# board-ext.net
KiCad netlist of a schematic drawn in EAGLE
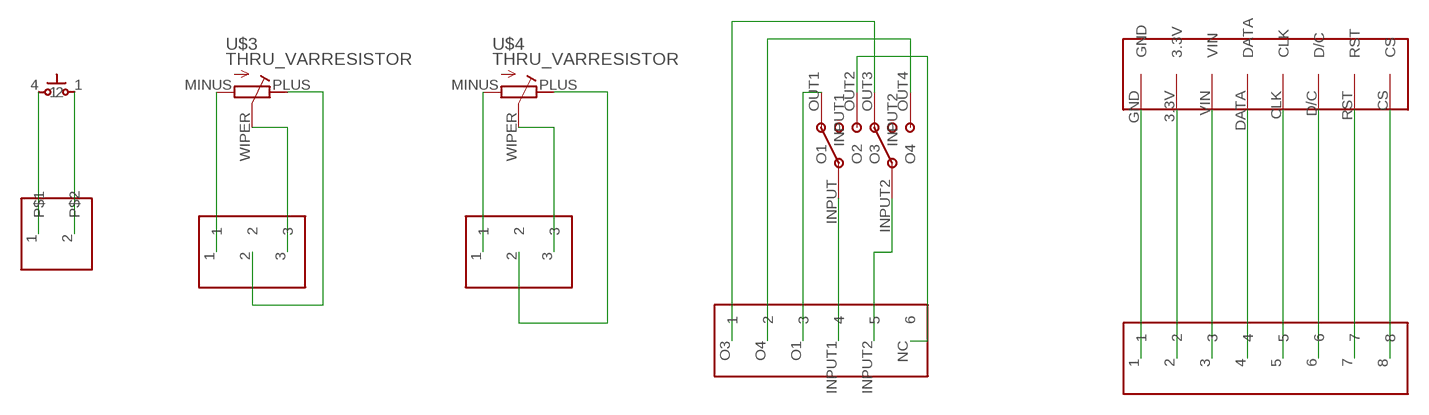
[diagram p0: schematic, sheet 1]

(export (version "E")
  (design (tool "Eeschema 10.0.6"))
  (components
    (comp (ref "U$1")
      (value "1X02")
      (footprint "eagle-import:1X02")
      (libsource (lib "eagle-import") (part "1X02"))
    )
    (comp (ref "U$2")
      (value "BUTTON_THRU")
      (footprint "eagle-import:PUSHBTN")
      (libsource (lib "eagle-import") (part "BUTTON_THRU"))
    )
    (comp (ref "U$3")
      (value "THRU_VARRESISTOR")
      (footprint "eagle-import:POT")
      (libsource (lib "eagle-import") (part "THRU_VARRESISTOR"))
    )
    (comp (ref "U$4")
      (value "THRU_VARRESISTOR")
      (footprint "eagle-import:POT")
      (libsource (lib "eagle-import") (part "THRU_VARRESISTOR"))
    )
    (comp (ref "U$5")
      (value "1X03")
      (footprint "eagle-import:1X03")
      (libsource (lib "eagle-import") (part "1X03"))
    )
    (comp (ref "U$6")
      (value "1X03")
      (footprint "eagle-import:1X03")
      (libsource (lib "eagle-import") (part "1X03"))
    )
    (comp (ref "U$7")
      (value "SWITCH_THRU")
      (footprint "eagle-import:DPDT")
      (libsource (lib "eagle-import") (part "SWITCH_THRU"))
    )
    (comp (ref "U$8")
      (value "1X06")
      (footprint "eagle-import:SWITCHHEAD")
      (libsource (lib "eagle-import") (part "1X06"))
    )
    (comp (ref "U$9")
      (value "OLED_THRU")
      (footprint "eagle-import:OLED_THRU")
      (libsource (lib "eagle-import") (part "OLED_THRU"))
    )
    (comp (ref "U$10")
      (value "1X08")
      (footprint "eagle-import:1X08")
      (libsource (lib "eagle-import") (part "1X08"))
    )
  )
  (nets
    (net (code "1") (name "Net-(U$1-P$1)") (class "Default")
      (node (ref "U$1") (pin "1") (pinfunction "P$1_1") (pintype "bidirectional"))
      (node (ref "U$2") (pin "4") (pinfunction "2_4") (pintype "bidirectional"))
    )
    (net (code "2") (name "Net-(U$1-P$2)") (class "Default")
      (node (ref "U$1") (pin "2") (pinfunction "P$2_2") (pintype "bidirectional"))
      (node (ref "U$2") (pin "1") (pinfunction "1_1") (pintype "bidirectional"))
    )
    (net (code "3") (name "Net-(U$3-PadMINUS)") (class "Default")
      (node (ref "U$3") (pin "MINUS") (pinfunction "MINUS_MINUS") (pintype "bidirectional"))
      (node (ref "U$5") (pin "1") (pinfunction "1_1") (pintype "bidirectional"))
    )
    (net (code "4") (name "Net-(U$3-PadPLUS)") (class "Default")
      (node (ref "U$3") (pin "PLUS") (pinfunction "PLUS_PLUS") (pintype "bidirectional"))
      (node (ref "U$5") (pin "2") (pinfunction "2_2") (pintype "bidirectional"))
    )
    (net (code "5") (name "Net-(U$3-PadWIPER)") (class "Default")
      (node (ref "U$3") (pin "WIPER") (pinfunction "WIPER_WIPER") (pintype "bidirectional"))
      (node (ref "U$5") (pin "3") (pinfunction "3_3") (pintype "bidirectional"))
    )
    (net (code "6") (name "Net-(U$4-PadMINUS)") (class "Default")
      (node (ref "U$4") (pin "MINUS") (pinfunction "MINUS_MINUS") (pintype "bidirectional"))
      (node (ref "U$6") (pin "1") (pinfunction "1_1") (pintype "bidirectional"))
    )
    (net (code "7") (name "Net-(U$4-PadPLUS)") (class "Default")
      (node (ref "U$4") (pin "PLUS") (pinfunction "PLUS_PLUS") (pintype "bidirectional"))
      (node (ref "U$6") (pin "2") (pinfunction "2_2") (pintype "bidirectional"))
    )
    (net (code "8") (name "Net-(U$4-PadWIPER)") (class "Default")
      (node (ref "U$4") (pin "WIPER") (pinfunction "WIPER_WIPER") (pintype "bidirectional"))
      (node (ref "U$6") (pin "3") (pinfunction "3_3") (pintype "bidirectional"))
    )
    (net (code "9") (name "Net-(U$7-INPUT1)") (class "Default")
      (node (ref "U$7") (pin "INPUT") (pinfunction "INPUT1_INPUT") (pintype "bidirectional"))
      (node (ref "U$8") (pin "INPUT1") (pinfunction "4_INPUT1") (pintype "bidirectional"))
    )
    (net (code "10") (name "Net-(U$7-O1)") (class "Default")
      (node (ref "U$7") (pin "OUT1") (pinfunction "O1_OUT1") (pintype "bidirectional"))
      (node (ref "U$8") (pin "O1") (pinfunction "3_O1") (pintype "bidirectional"))
    )
    (net (code "11") (name "Net-(U$7-O2)") (class "Default")
      (node (ref "U$7") (pin "OUT2") (pinfunction "O2_OUT2") (pintype "bidirectional"))
      (node (ref "U$8") (pin "NC") (pinfunction "6_NC") (pintype "bidirectional"))
    )
    (net (code "12") (name "Net-(U$7-O3)") (class "Default")
      (node (ref "U$7") (pin "OUT3") (pinfunction "O3_OUT3") (pintype "bidirectional"))
      (node (ref "U$8") (pin "O3") (pinfunction "1_O3") (pintype "bidirectional"))
    )
    (net (code "13") (name "Net-(U$7-O4)") (class "Default")
      (node (ref "U$7") (pin "OUT4") (pinfunction "O4_OUT4") (pintype "bidirectional"))
      (node (ref "U$8") (pin "O4") (pinfunction "2_O4") (pintype "bidirectional"))
    )
    (net (code "14") (name "Net-(U$8-5)") (class "Default")
      (node (ref "U$7") (pin "INPUT2") (pinfunction "INPUT2_INPUT2") (pintype "bidirectional"))
      (node (ref "U$8") (pin "INPUT2") (pinfunction "5_INPUT2") (pintype "bidirectional"))
    )
    (net (code "15") (name "Net-(U$10-Pad1)") (class "Default")
      (node (ref "U$10") (pin "1") (pinfunction "1_1") (pintype "bidirectional"))
      (node (ref "U$9") (pin "GND") (pinfunction "GND_GND") (pintype "bidirectional"))
    )
    (net (code "16") (name "Net-(U$10-Pad2)") (class "Default")
      (node (ref "U$10") (pin "2") (pinfunction "2_2") (pintype "bidirectional"))
      (node (ref "U$9") (pin "3.3V") (pinfunction "3.3V_3.3V") (pintype "bidirectional"))
    )
    (net (code "17") (name "Net-(U$10-Pad3)") (class "Default")
      (node (ref "U$10") (pin "3") (pinfunction "3_3") (pintype "bidirectional"))
      (node (ref "U$9") (pin "VIN") (pinfunction "VIN_VIN") (pintype "bidirectional"))
    )
    (net (code "18") (name "Net-(U$10-Pad4)") (class "Default")
      (node (ref "U$10") (pin "4") (pinfunction "4_4") (pintype "bidirectional"))
      (node (ref "U$9") (pin "DATA") (pinfunction "DATA_DATA") (pintype "bidirectional"))
    )
    (net (code "19") (name "Net-(U$10-Pad5)") (class "Default")
      (node (ref "U$10") (pin "5") (pinfunction "5_5") (pintype "bidirectional"))
      (node (ref "U$9") (pin "CLK") (pinfunction "CLK_CLK") (pintype "bidirectional"))
    )
    (net (code "20") (name "Net-(U$10-Pad6)") (class "Default")
      (node (ref "U$10") (pin "6") (pinfunction "6_6") (pintype "bidirectional"))
      (node (ref "U$9") (pin "D/C") (pinfunction "D/C_D/C") (pintype "bidirectional"))
    )
    (net (code "21") (name "Net-(U$10-Pad7)") (class "Default")
      (node (ref "U$10") (pin "7") (pinfunction "7_7") (pintype "bidirectional"))
      (node (ref "U$9") (pin "RST") (pinfunction "RST_RST") (pintype "bidirectional"))
    )
    (net (code "22") (name "Net-(U$10-Pad8)") (class "Default")
      (node (ref "U$10") (pin "8") (pinfunction "8_8") (pintype "bidirectional"))
      (node (ref "U$9") (pin "CS") (pinfunction "CS_CS") (pintype "bidirectional"))
    )
  )
)
